# ETH.net
KiCad netlist of a schematic drawn in Altium Designer
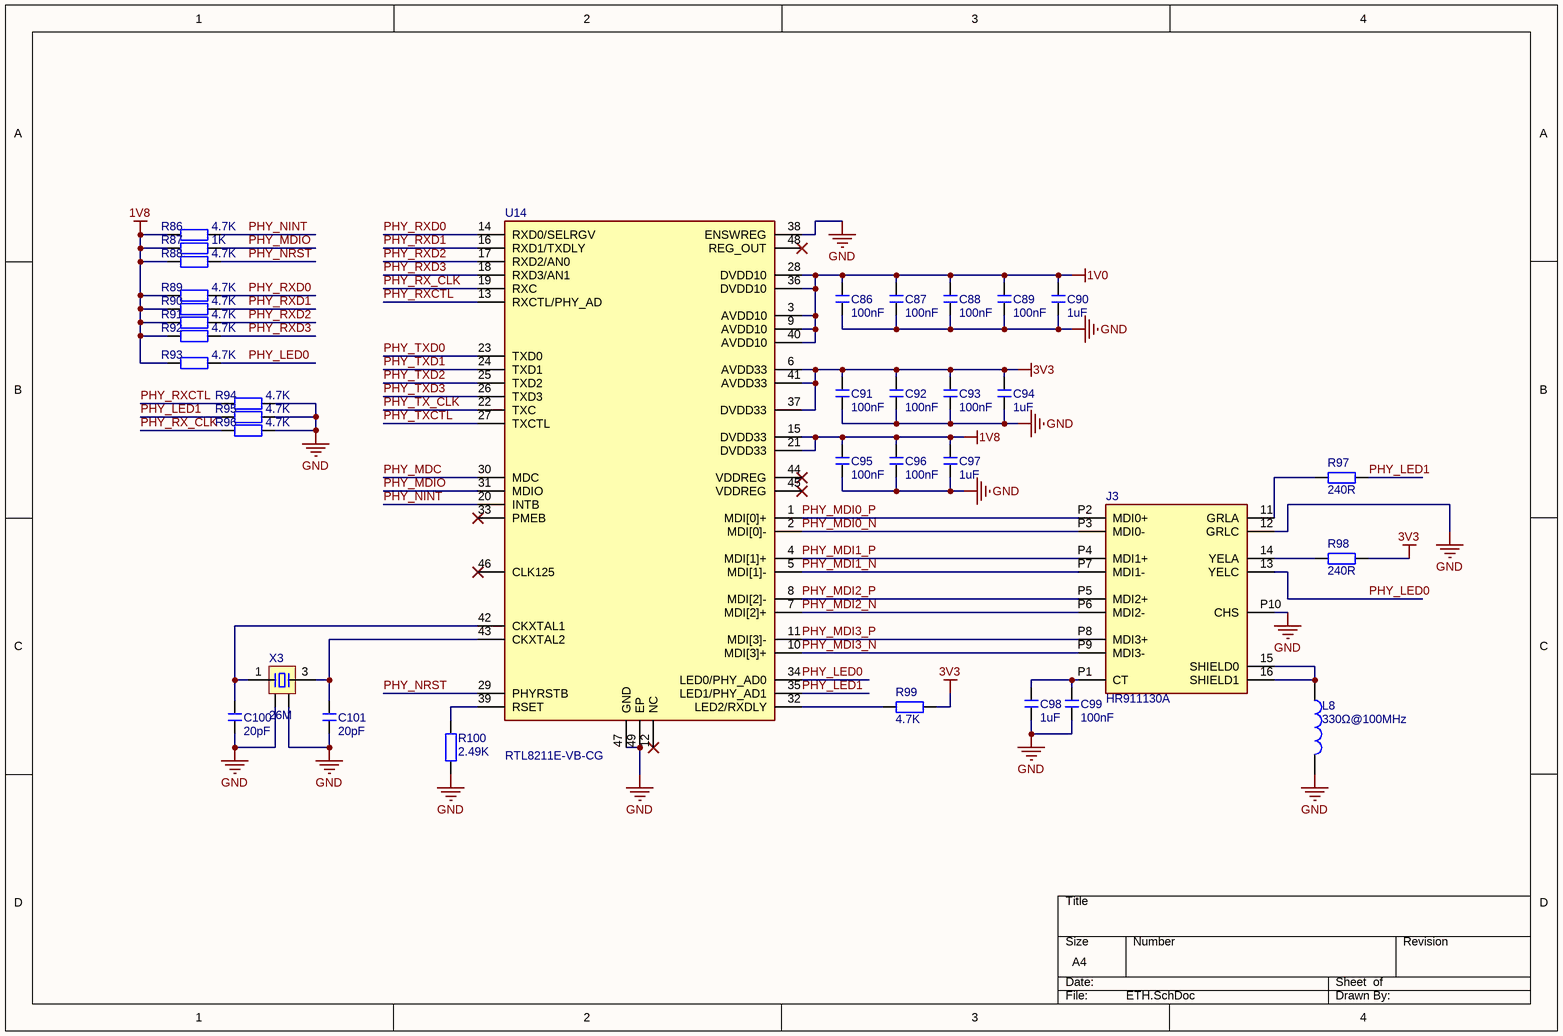
[diagram p0: ETH.SchDoc]

(export (version "E")
  (design (tool "Eeschema 10.0.6"))
  (components
    (comp (ref "C86")
      (value "100nF")
      (footprint "C 0402_L")
      (description "无极性贴片电容")
      (fields (field (name "版权归属") "源创客"))
      (libsource (lib "3.1   - 电阻-电容-电感") (part "C"))
    )
    (comp (ref "C87")
      (value "100nF")
      (footprint "C 0402_L")
      (description "无极性贴片电容")
      (fields (field (name "版权归属") "源创客"))
      (libsource (lib "3.1   - 电阻-电容-电感") (part "C"))
    )
    (comp (ref "C88")
      (value "100nF")
      (footprint "C 0402_L")
      (description "无极性贴片电容")
      (fields (field (name "版权归属") "源创客"))
      (libsource (lib "3.1   - 电阻-电容-电感") (part "C"))
    )
    (comp (ref "C89")
      (value "100nF")
      (footprint "C 0402_L")
      (description "无极性贴片电容")
      (fields (field (name "版权归属") "源创客"))
      (libsource (lib "3.1   - 电阻-电容-电感") (part "C"))
    )
    (comp (ref "C90")
      (value "1uF")
      (footprint "C 0402_L")
      (description "无极性贴片电容")
      (fields (field (name "版权归属") "源创客"))
      (libsource (lib "3.1   - 电阻-电容-电感") (part "C"))
    )
    (comp (ref "C91")
      (value "100nF")
      (footprint "C 0402_L")
      (description "无极性贴片电容")
      (fields (field (name "版权归属") "源创客"))
      (libsource (lib "3.1   - 电阻-电容-电感") (part "C"))
    )
    (comp (ref "C92")
      (value "100nF")
      (footprint "C 0402_L")
      (description "无极性贴片电容")
      (fields (field (name "版权归属") "源创客"))
      (libsource (lib "3.1   - 电阻-电容-电感") (part "C"))
    )
    (comp (ref "C93")
      (value "100nF")
      (footprint "C 0402_L")
      (description "无极性贴片电容")
      (fields (field (name "版权归属") "源创客"))
      (libsource (lib "3.1   - 电阻-电容-电感") (part "C"))
    )
    (comp (ref "C94")
      (value "1uF")
      (footprint "C 0402_L")
      (description "无极性贴片电容")
      (fields (field (name "版权归属") "源创客"))
      (libsource (lib "3.1   - 电阻-电容-电感") (part "C"))
    )
    (comp (ref "C95")
      (value "100nF")
      (footprint "C 0402_L")
      (description "无极性贴片电容")
      (fields (field (name "版权归属") "源创客"))
      (libsource (lib "3.1   - 电阻-电容-电感") (part "C"))
    )
    (comp (ref "C96")
      (value "100nF")
      (footprint "C 0402_L")
      (description "无极性贴片电容")
      (fields (field (name "版权归属") "源创客"))
      (libsource (lib "3.1   - 电阻-电容-电感") (part "C"))
    )
    (comp (ref "C97")
      (value "1uF")
      (footprint "C 0402_L")
      (description "无极性贴片电容")
      (fields (field (name "版权归属") "源创客"))
      (libsource (lib "3.1   - 电阻-电容-电感") (part "C"))
    )
    (comp (ref "C98")
      (value "1uF")
      (footprint "C 0402_L")
      (description "无极性贴片电容")
      (fields (field (name "版权归属") "源创客"))
      (libsource (lib "3.1   - 电阻-电容-电感") (part "C"))
    )
    (comp (ref "C99")
      (value "100nF")
      (footprint "C 0402_L")
      (description "无极性贴片电容")
      (fields (field (name "版权归属") "源创客"))
      (libsource (lib "3.1   - 电阻-电容-电感") (part "C"))
    )
    (comp (ref "C100")
      (value "20pF")
      (footprint "C 0805_L")
      (description "无极性贴片电容")
      (fields (field (name "版权归属") "源创客"))
      (libsource (lib "3.1   - 电阻-电容-电感") (part "C"))
    )
    (comp (ref "C101")
      (value "20pF")
      (footprint "C 0805_L")
      (description "无极性贴片电容")
      (fields (field (name "版权归属") "源创客"))
      (libsource (lib "3.1   - 电阻-电容-电感") (part "C"))
    )
    (comp (ref "J3")
      (value "HR911130A")
      (footprint "通讯接口:HR911130A")
      (description "千兆以太网带变压器")
      (libsource (lib "4.1   - 接口类") (part "HR911130A"))
    )
    (comp (ref "L8")
      (value "330Ω@100MHz")
      (footprint "L 0805")
      (description "小功率贴片电感")
      (fields (field (name "版权归属") "源创客"))
      (libsource (lib "3.1   - 电阻-电容-电感") (part "L"))
    )
    (comp (ref "R86")
      (value "4.7K")
      (footprint "R 0402_L")
      (description "贴片电阻")
      (fields (field (name "版权归属") "源创客"))
      (libsource (lib "3.1   - 电阻-电容-电感") (part "R"))
    )
    (comp (ref "R87")
      (value "1K")
      (footprint "R 0402_L")
      (description "贴片电阻")
      (fields (field (name "版权归属") "源创客"))
      (libsource (lib "3.1   - 电阻-电容-电感") (part "R"))
    )
    (comp (ref "R88")
      (value "4.7K")
      (footprint "R 0402_L")
      (description "贴片电阻")
      (fields (field (name "版权归属") "源创客"))
      (libsource (lib "3.1   - 电阻-电容-电感") (part "R"))
    )
    (comp (ref "R89")
      (value "4.7K")
      (footprint "R 0402_L")
      (description "贴片电阻")
      (fields (field (name "版权归属") "源创客"))
      (libsource (lib "3.1   - 电阻-电容-电感") (part "R"))
    )
    (comp (ref "R90")
      (value "4.7K")
      (footprint "R 0402_L")
      (description "贴片电阻")
      (fields (field (name "版权归属") "源创客"))
      (libsource (lib "3.1   - 电阻-电容-电感") (part "R"))
    )
    (comp (ref "R91")
      (value "4.7K")
      (footprint "R 0402_L")
      (description "贴片电阻")
      (fields (field (name "版权归属") "源创客"))
      (libsource (lib "3.1   - 电阻-电容-电感") (part "R"))
    )
    (comp (ref "R92")
      (value "4.7K")
      (footprint "R 0402_L")
      (description "贴片电阻")
      (fields (field (name "版权归属") "源创客"))
      (libsource (lib "3.1   - 电阻-电容-电感") (part "R"))
    )
    (comp (ref "R93")
      (value "4.7K")
      (footprint "R 0402_L")
      (description "贴片电阻")
      (fields (field (name "版权归属") "源创客"))
      (libsource (lib "3.1   - 电阻-电容-电感") (part "R"))
    )
    (comp (ref "R94")
      (value "4.7K")
      (footprint "R 0402_L")
      (description "贴片电阻")
      (fields (field (name "版权归属") "源创客"))
      (libsource (lib "3.1   - 电阻-电容-电感") (part "R"))
    )
    (comp (ref "R95")
      (value "4.7K")
      (footprint "R 0402_L")
      (description "贴片电阻")
      (fields (field (name "版权归属") "源创客"))
      (libsource (lib "3.1   - 电阻-电容-电感") (part "R"))
    )
    (comp (ref "R96")
      (value "4.7K")
      (footprint "R 0402_L")
      (description "贴片电阻")
      (fields (field (name "版权归属") "源创客"))
      (libsource (lib "3.1   - 电阻-电容-电感") (part "R"))
    )
    (comp (ref "R97")
      (value "240R")
      (footprint "R 0805_L")
      (description "贴片电阻")
      (fields (field (name "版权归属") "源创客"))
      (libsource (lib "3.1   - 电阻-电容-电感") (part "R"))
    )
    (comp (ref "R98")
      (value "240R")
      (footprint "R 0805_L")
      (description "贴片电阻")
      (fields (field (name "版权归属") "源创客"))
      (libsource (lib "3.1   - 电阻-电容-电感") (part "R"))
    )
    (comp (ref "R99")
      (value "4.7K")
      (footprint "R 0402_L")
      (description "贴片电阻")
      (fields (field (name "版权归属") "源创客"))
      (libsource (lib "3.1   - 电阻-电容-电感") (part "R"))
    )
    (comp (ref "R100")
      (value "2.49K")
      (footprint "R 0402_L")
      (description "贴片电阻")
      (fields (field (name "版权归属") "源创客"))
      (libsource (lib "3.1   - 电阻-电容-电感") (part "R"))
    )
    (comp (ref "U14")
      (value "RTL8211E-VB-CG")
      (footprint "QFN48 7X7_L")
      (description "以太网芯片")
      (libsource (lib "1.1   - IC芯片") (part "RTL8211E-VB-CG"))
    )
    (comp (ref "X3")
      (value "26M")
      (footprint "OSC 1612-4P")
      (description "4脚无源晶振")
      (fields (field (name "版权归属") "源创客"))
      (libsource (lib "10.1 - 保险丝-晶振") (part "XTAL-4P"))
    )
  )
  (nets
    (net (code "1") (name "/PHY_LED0") (class "Default")
      (node (ref "J3") (pin "13") (pinfunction "YELC_13") (pintype "passive"))
      (node (ref "R93") (pin "1") (pinfunction "1_1") (pintype "passive"))
      (node (ref "U14") (pin "34") (pinfunction "LED0/PHY_AD0_34") (pintype "passive"))
    )
    (net (code "2") (name "/PHY_LED1") (class "Default")
      (node (ref "R95") (pin "2") (pinfunction "2_2") (pintype "passive"))
      (node (ref "R97") (pin "1") (pinfunction "1_1") (pintype "passive"))
      (node (ref "U14") (pin "35") (pinfunction "LED1/PHY_AD1_35") (pintype "passive"))
    )
    (net (code "3") (name "/PHY_MDC") (class "Default")
      (node (ref "U14") (pin "30") (pinfunction "MDC_30") (pintype "passive"))
    )
    (net (code "4") (name "/PHY_MDI0_N") (class "Default")
      (node (ref "J3") (pin "P3") (pinfunction "MDI0-_P3") (pintype "passive"))
      (node (ref "U14") (pin "2") (pinfunction "MDI[0]-_2") (pintype "passive"))
    )
    (net (code "5") (name "/PHY_MDI0_P") (class "Default")
      (node (ref "J3") (pin "P2") (pinfunction "MDI0+_P2") (pintype "passive"))
      (node (ref "U14") (pin "1") (pinfunction "MDI[0]+_1") (pintype "passive"))
    )
    (net (code "6") (name "/PHY_MDI1_N") (class "Default")
      (node (ref "J3") (pin "P7") (pinfunction "MDI1-_P7") (pintype "passive"))
      (node (ref "U14") (pin "5") (pinfunction "MDI[1]-_5") (pintype "passive"))
    )
    (net (code "7") (name "/PHY_MDI1_P") (class "Default")
      (node (ref "J3") (pin "P4") (pinfunction "MDI1+_P4") (pintype "passive"))
      (node (ref "U14") (pin "4") (pinfunction "MDI[1]+_4") (pintype "passive"))
    )
    (net (code "8") (name "/PHY_MDI2_N") (class "Default")
      (node (ref "J3") (pin "P6") (pinfunction "MDI2-_P6") (pintype "passive"))
      (node (ref "U14") (pin "7") (pinfunction "MDI[2]+_7") (pintype "passive"))
    )
    (net (code "9") (name "/PHY_MDI2_P") (class "Default")
      (node (ref "J3") (pin "P5") (pinfunction "MDI2+_P5") (pintype "passive"))
      (node (ref "U14") (pin "8") (pinfunction "MDI[2]-_8") (pintype "passive"))
    )
    (net (code "10") (name "/PHY_MDI3_N") (class "Default")
      (node (ref "J3") (pin "P9") (pinfunction "MDI3-_P9") (pintype "passive"))
      (node (ref "U14") (pin "10") (pinfunction "MDI[3]+_10") (pintype "passive"))
    )
    (net (code "11") (name "/PHY_MDI3_P") (class "Default")
      (node (ref "J3") (pin "P8") (pinfunction "MDI3+_P8") (pintype "passive"))
      (node (ref "U14") (pin "11") (pinfunction "MDI[3]-_11") (pintype "passive"))
    )
    (net (code "12") (name "/PHY_MDIO") (class "Default")
      (node (ref "R87") (pin "1") (pinfunction "1_1") (pintype "passive"))
      (node (ref "U14") (pin "31") (pinfunction "MDIO_31") (pintype "passive"))
    )
    (net (code "13") (name "/PHY_NINT") (class "Default")
      (node (ref "R86") (pin "1") (pinfunction "1_1") (pintype "passive"))
      (node (ref "U14") (pin "20") (pinfunction "INTB_20") (pintype "passive"))
    )
    (net (code "14") (name "/PHY_NRST") (class "Default")
      (node (ref "R88") (pin "1") (pinfunction "1_1") (pintype "passive"))
      (node (ref "U14") (pin "29") (pinfunction "PHYRSTB_29") (pintype "passive"))
    )
    (net (code "15") (name "/PHY_RXCTL") (class "Default")
      (node (ref "R94") (pin "2") (pinfunction "2_2") (pintype "passive"))
      (node (ref "U14") (pin "13") (pinfunction "RXCTL/PHY_AD_13") (pintype "passive"))
    )
    (net (code "16") (name "/PHY_RXD0") (class "Default")
      (node (ref "R89") (pin "1") (pinfunction "1_1") (pintype "passive"))
      (node (ref "U14") (pin "14") (pinfunction "RXD0/SELRGV_14") (pintype "passive"))
    )
    (net (code "17") (name "/PHY_RXD1") (class "Default")
      (node (ref "R90") (pin "1") (pinfunction "1_1") (pintype "passive"))
      (node (ref "U14") (pin "16") (pinfunction "RXD1/TXDLY_16") (pintype "passive"))
    )
    (net (code "18") (name "/PHY_RXD2") (class "Default")
      (node (ref "R91") (pin "1") (pinfunction "1_1") (pintype "passive"))
      (node (ref "U14") (pin "17") (pinfunction "RXD2/AN0_17") (pintype "passive"))
    )
    (net (code "19") (name "/PHY_RXD3") (class "Default")
      (node (ref "R92") (pin "1") (pinfunction "1_1") (pintype "passive"))
      (node (ref "U14") (pin "18") (pinfunction "RXD3/AN1_18") (pintype "passive"))
    )
    (net (code "20") (name "/PHY_RX_CLK") (class "Default")
      (node (ref "R96") (pin "2") (pinfunction "2_2") (pintype "passive"))
      (node (ref "U14") (pin "19") (pinfunction "RXC_19") (pintype "passive"))
    )
    (net (code "21") (name "/PHY_TXCTL") (class "Default")
      (node (ref "U14") (pin "27") (pinfunction "TXCTL_27") (pintype "passive"))
    )
    (net (code "22") (name "/PHY_TXD0") (class "Default")
      (node (ref "U14") (pin "23") (pinfunction "TXD0_23") (pintype "passive"))
    )
    (net (code "23") (name "/PHY_TXD1") (class "Default")
      (node (ref "U14") (pin "24") (pinfunction "TXD1_24") (pintype "passive"))
    )
    (net (code "24") (name "/PHY_TXD2") (class "Default")
      (node (ref "U14") (pin "25") (pinfunction "TXD2_25") (pintype "passive"))
    )
    (net (code "25") (name "/PHY_TXD3") (class "Default")
      (node (ref "U14") (pin "26") (pinfunction "TXD3_26") (pintype "passive"))
    )
    (net (code "26") (name "/PHY_TX_CLK") (class "Default")
      (node (ref "U14") (pin "22") (pinfunction "TXC_22") (pintype "passive"))
    )
    (net (code "27") (name "1V0") (class "Default")
      (node (ref "C86") (pin "2") (pinfunction "2_2") (pintype "passive"))
      (node (ref "C87") (pin "2") (pinfunction "2_2") (pintype "passive"))
      (node (ref "C88") (pin "2") (pinfunction "2_2") (pintype "passive"))
      (node (ref "C89") (pin "2") (pinfunction "2_2") (pintype "passive"))
      (node (ref "C90") (pin "2") (pinfunction "2_2") (pintype "passive"))
      (node (ref "U14") (pin "28") (pinfunction "DVDD10_28") (pintype "passive"))
      (node (ref "U14") (pin "3") (pinfunction "AVDD10_3") (pintype "passive"))
      (node (ref "U14") (pin "36") (pinfunction "DVDD10_36") (pintype "passive"))
      (node (ref "U14") (pin "40") (pinfunction "AVDD10_40") (pintype "passive"))
      (node (ref "U14") (pin "9") (pinfunction "AVDD10_9") (pintype "passive"))
    )
    (net (code "28") (name "1V8") (class "Default")
      (node (ref "C95") (pin "2") (pinfunction "2_2") (pintype "passive"))
      (node (ref "C96") (pin "2") (pinfunction "2_2") (pintype "passive"))
      (node (ref "C97") (pin "2") (pinfunction "2_2") (pintype "passive"))
      (node (ref "R86") (pin "2") (pinfunction "2_2") (pintype "passive"))
      (node (ref "R87") (pin "2") (pinfunction "2_2") (pintype "passive"))
      (node (ref "R88") (pin "2") (pinfunction "2_2") (pintype "passive"))
      (node (ref "R89") (pin "2") (pinfunction "2_2") (pintype "passive"))
      (node (ref "R90") (pin "2") (pinfunction "2_2") (pintype "passive"))
      (node (ref "R91") (pin "2") (pinfunction "2_2") (pintype "passive"))
      (node (ref "R92") (pin "2") (pinfunction "2_2") (pintype "passive"))
      (node (ref "R93") (pin "2") (pinfunction "2_2") (pintype "passive"))
      (node (ref "U14") (pin "15") (pinfunction "DVDD33_15") (pintype "passive"))
      (node (ref "U14") (pin "21") (pinfunction "DVDD33_21") (pintype "passive"))
    )
    (net (code "29") (name "3V3") (class "Default")
      (node (ref "C91") (pin "2") (pinfunction "2_2") (pintype "passive"))
      (node (ref "C92") (pin "2") (pinfunction "2_2") (pintype "passive"))
      (node (ref "C93") (pin "2") (pinfunction "2_2") (pintype "passive"))
      (node (ref "C94") (pin "2") (pinfunction "2_2") (pintype "passive"))
      (node (ref "R98") (pin "1") (pinfunction "1_1") (pintype "passive"))
      (node (ref "R99") (pin "1") (pinfunction "1_1") (pintype "passive"))
      (node (ref "U14") (pin "37") (pinfunction "DVDD33_37") (pintype "passive"))
      (node (ref "U14") (pin "41") (pinfunction "AVDD33_41") (pintype "passive"))
      (node (ref "U14") (pin "6") (pinfunction "AVDD33_6") (pintype "passive"))
    )
    (net (code "30") (name "GND") (class "Default")
      (node (ref "C100") (pin "1") (pinfunction "1_1") (pintype "passive"))
      (node (ref "C101") (pin "1") (pinfunction "1_1") (pintype "passive"))
      (node (ref "C86") (pin "1") (pinfunction "1_1") (pintype "passive"))
      (node (ref "C87") (pin "1") (pinfunction "1_1") (pintype "passive"))
      (node (ref "C88") (pin "1") (pinfunction "1_1") (pintype "passive"))
      (node (ref "C89") (pin "1") (pinfunction "1_1") (pintype "passive"))
      (node (ref "C90") (pin "1") (pinfunction "1_1") (pintype "passive"))
      (node (ref "C91") (pin "1") (pinfunction "1_1") (pintype "passive"))
      (node (ref "C92") (pin "1") (pinfunction "1_1") (pintype "passive"))
      (node (ref "C93") (pin "1") (pinfunction "1_1") (pintype "passive"))
      (node (ref "C94") (pin "1") (pinfunction "1_1") (pintype "passive"))
      (node (ref "C95") (pin "1") (pinfunction "1_1") (pintype "passive"))
      (node (ref "C96") (pin "1") (pinfunction "1_1") (pintype "passive"))
      (node (ref "C97") (pin "1") (pinfunction "1_1") (pintype "passive"))
      (node (ref "C98") (pin "1") (pinfunction "1_1") (pintype "passive"))
      (node (ref "C99") (pin "1") (pinfunction "1_1") (pintype "passive"))
      (node (ref "J3") (pin "12") (pinfunction "GRLC_12") (pintype "passive"))
      (node (ref "J3") (pin "P10") (pinfunction "CHS_P10") (pintype "passive"))
      (node (ref "L8") (pin "2") (pinfunction "2_2") (pintype "passive"))
      (node (ref "R100") (pin "1") (pinfunction "1_1") (pintype "passive"))
      (node (ref "R94") (pin "1") (pinfunction "1_1") (pintype "passive"))
      (node (ref "R95") (pin "1") (pinfunction "1_1") (pintype "passive"))
      (node (ref "R96") (pin "1") (pinfunction "1_1") (pintype "passive"))
      (node (ref "U14") (pin "38") (pinfunction "ENSWREG_38") (pintype "passive"))
      (node (ref "U14") (pin "47") (pinfunction "GND_47") (pintype "passive"))
      (node (ref "U14") (pin "49") (pinfunction "EP_49") (pintype "passive"))
      (node (ref "X3") (pin "2") (pinfunction "2_2") (pintype "passive"))
      (node (ref "X3") (pin "4") (pinfunction "4_4") (pintype "passive"))
    )
    (net (code "31") (name "Net-(J3-CT)") (class "Default")
      (node (ref "C98") (pin "2") (pinfunction "2_2") (pintype "passive"))
      (node (ref "C99") (pin "2") (pinfunction "2_2") (pintype "passive"))
      (node (ref "J3") (pin "P1") (pinfunction "CT_P1") (pintype "passive"))
    )
    (net (code "32") (name "Net-(J3-GRLA)") (class "Default")
      (node (ref "J3") (pin "11") (pinfunction "GRLA_11") (pintype "passive"))
      (node (ref "R97") (pin "2") (pinfunction "2_2") (pintype "passive"))
    )
    (net (code "33") (name "Net-(J3-SHIELD0)") (class "Default")
      (node (ref "J3") (pin "15") (pinfunction "SHIELD0_15") (pintype "passive"))
      (node (ref "J3") (pin "16") (pinfunction "SHIELD1_16") (pintype "passive"))
      (node (ref "L8") (pin "1") (pinfunction "1_1") (pintype "passive"))
    )
    (net (code "34") (name "Net-(J3-YELA)") (class "Default")
      (node (ref "J3") (pin "14") (pinfunction "YELA_14") (pintype "passive"))
      (node (ref "R98") (pin "2") (pinfunction "2_2") (pintype "passive"))
    )
    (net (code "35") (name "Net-(U14-CKXTAL1)") (class "Default")
      (node (ref "C100") (pin "2") (pinfunction "2_2") (pintype "passive"))
      (node (ref "U14") (pin "42") (pinfunction "CKXTAL1_42") (pintype "passive"))
      (node (ref "X3") (pin "1") (pinfunction "1_1") (pintype "passive"))
    )
    (net (code "36") (name "Net-(U14-CKXTAL2)") (class "Default")
      (node (ref "C101") (pin "2") (pinfunction "2_2") (pintype "passive"))
      (node (ref "U14") (pin "43") (pinfunction "CKXTAL2_43") (pintype "passive"))
      (node (ref "X3") (pin "3") (pinfunction "3_3") (pintype "passive"))
    )
    (net (code "37") (name "Net-(U14-LED2{slash}RXDLY)") (class "Default")
      (node (ref "R99") (pin "2") (pinfunction "2_2") (pintype "passive"))
      (node (ref "U14") (pin "32") (pinfunction "LED2/RXDLY_32") (pintype "passive"))
    )
    (net (code "38") (name "Net-(U14-RSET)") (class "Default")
      (node (ref "R100") (pin "2") (pinfunction "2_2") (pintype "passive"))
      (node (ref "U14") (pin "39") (pinfunction "RSET_39") (pintype "passive"))
    )
    (net (code "39") (name "unconnected-(U14-CLK125-Pad46)") (class "Default")
      (node (ref "U14") (pin "46") (pinfunction "CLK125_46") (pintype "passive+no_connect"))
    )
    (net (code "40") (name "unconnected-(U14-NC-Pad12)") (class "Default")
      (node (ref "U14") (pin "12") (pinfunction "NC_12") (pintype "passive+no_connect"))
    )
    (net (code "41") (name "unconnected-(U14-PMEB-Pad33)") (class "Default")
      (node (ref "U14") (pin "33") (pinfunction "PMEB_33") (pintype "passive+no_connect"))
    )
    (net (code "42") (name "unconnected-(U14-REG_OUT-Pad48)") (class "Default")
      (node (ref "U14") (pin "48") (pinfunction "REG_OUT_48") (pintype "passive+no_connect"))
    )
    (net (code "43") (name "unconnected-(U14-VDDREG-Pad44)") (class "Default")
      (node (ref "U14") (pin "44") (pinfunction "VDDREG_44") (pintype "passive+no_connect"))
    )
    (net (code "44") (name "unconnected-(U14-VDDREG-Pad45)") (class "Default")
      (node (ref "U14") (pin "45") (pinfunction "VDDREG_45") (pintype "passive+no_connect"))
    )
  )
)
